# PCB.net
KiCad netlist of a schematic drawn in EAGLE
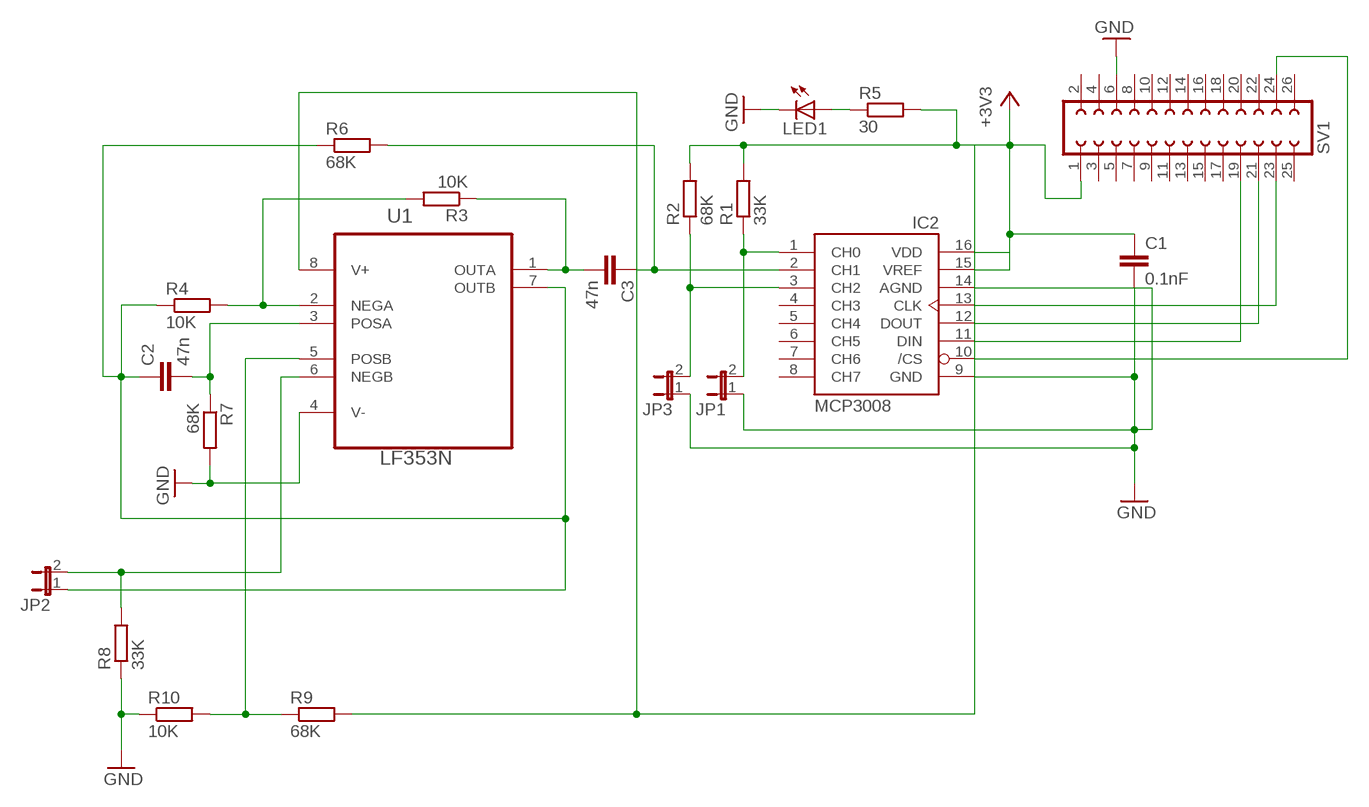
[diagram p0: schematic, sheet 1]

(export (version "E")
  (design (tool "Eeschema 10.0.6"))
  (components
    (comp (ref "C1")
      (value "0.1nF")
      (footprint "eagle-import:C050-035X075")
      (libsource (lib "eagle-import") (part "C-EU050-035X075"))
    )
    (comp (ref "C2")
      (value "47n")
      (footprint "eagle-import:C2.5-5")
      (libsource (lib "eagle-import") (part "C2.5/5"))
    )
    (comp (ref "C3")
      (value "47n")
      (footprint "eagle-import:C2.5-5")
      (libsource (lib "eagle-import") (part "C2.5/5"))
    )
    (comp (ref "IC2")
      (value "MCP3008")
      (footprint "eagle-import:DIL16")
      (libsource (lib "eagle-import") (part "MCP3008"))
    )
    (comp (ref "JP1")
      (value "JP1E")
      (footprint "eagle-import:JP1")
      (libsource (lib "eagle-import") (part "JP1E"))
    )
    (comp (ref "JP2")
      (value "JP1E")
      (footprint "eagle-import:JP1")
      (libsource (lib "eagle-import") (part "JP1E"))
    )
    (comp (ref "JP3")
      (value "JP1E")
      (footprint "eagle-import:JP1")
      (libsource (lib "eagle-import") (part "JP1E"))
    )
    (comp (ref "LED1")
      (value "LED5MM")
      (footprint "eagle-import:LED5MM")
      (libsource (lib "eagle-import") (part "LED5MM"))
    )
    (comp (ref "R1")
      (value "33K")
      (footprint "eagle-import:0207_10")
      (libsource (lib "eagle-import") (part "R-EU_0207/10"))
    )
    (comp (ref "R2")
      (value "68K")
      (footprint "eagle-import:0207_10")
      (libsource (lib "eagle-import") (part "R-EU_0207/10"))
    )
    (comp (ref "R3")
      (value "10K")
      (footprint "eagle-import:0207_10")
      (libsource (lib "eagle-import") (part "R-EU_0207/10"))
    )
    (comp (ref "R4")
      (value "10K")
      (footprint "eagle-import:0207_10")
      (libsource (lib "eagle-import") (part "R-EU_0207/10"))
    )
    (comp (ref "R5")
      (value "30")
      (footprint "eagle-import:0207_10")
      (libsource (lib "eagle-import") (part "R-EU_0207/10"))
    )
    (comp (ref "R6")
      (value "68K")
      (footprint "eagle-import:0207_10")
      (libsource (lib "eagle-import") (part "R-EU_0207/10"))
    )
    (comp (ref "R7")
      (value "68K")
      (footprint "eagle-import:0207_10")
      (libsource (lib "eagle-import") (part "R-EU_0207/10"))
    )
    (comp (ref "R8")
      (value "33K")
      (footprint "eagle-import:0207_10")
      (libsource (lib "eagle-import") (part "R-EU_0207/10"))
    )
    (comp (ref "R9")
      (value "68K")
      (footprint "eagle-import:0207_10")
      (libsource (lib "eagle-import") (part "R-EU_0207/10"))
    )
    (comp (ref "R10")
      (value "10K")
      (footprint "eagle-import:0207_10")
      (libsource (lib "eagle-import") (part "R-EU_0207/10"))
    )
    (comp (ref "SV1")
      (value "FE13-2")
      (footprint "eagle-import:FE13-2")
      (libsource (lib "eagle-import") (part "FE13-2"))
    )
    (comp (ref "U1")
      (value "LF353N")
      (footprint "eagle-import:DIP254P762X508-8")
      (fields (field (name "MF") "MCM Electronics"))
      (libsource (lib "eagle-import") (part "LF353N"))
    )
  )
  (nets
    (net (code "1") (name "+3V3") (class "Default")
      (node (ref "C1") (pin "1") (pinfunction "1_1") (pintype "passive"))
      (node (ref "IC2") (pin "15") (pinfunction "VREF_15") (pintype "input"))
      (node (ref "IC2") (pin "16") (pinfunction "VDD_16") (pintype "power_in"))
      (node (ref "R1") (pin "2") (pinfunction "2_2") (pintype "passive"))
      (node (ref "R2") (pin "2") (pinfunction "2_2") (pintype "passive"))
      (node (ref "R5") (pin "2") (pinfunction "2_2") (pintype "passive"))
      (node (ref "R9") (pin "2") (pinfunction "2_2") (pintype "passive"))
      (node (ref "SV1") (pin "1") (pinfunction "1_1") (pintype "passive"))
      (node (ref "U1") (pin "8") (pinfunction "V+_8") (pintype "power_in"))
    )
    (net (code "2") (name "GND") (class "Default")
      (node (ref "C1") (pin "2") (pinfunction "2_2") (pintype "passive"))
      (node (ref "IC2") (pin "14") (pinfunction "AGND_14") (pintype "power_in"))
      (node (ref "IC2") (pin "9") (pinfunction "GND_9") (pintype "power_in"))
      (node (ref "JP1") (pin "1") (pinfunction "1_1") (pintype "passive"))
      (node (ref "JP3") (pin "1") (pinfunction "1_1") (pintype "passive"))
      (node (ref "LED1") (pin "K") (pinfunction "C_K") (pintype "passive"))
      (node (ref "R10") (pin "1") (pinfunction "1_1") (pintype "passive"))
      (node (ref "R7") (pin "2") (pinfunction "2_2") (pintype "passive"))
      (node (ref "R8") (pin "1") (pinfunction "1_1") (pintype "passive"))
      (node (ref "SV1") (pin "6") (pinfunction "6_6") (pintype "passive"))
      (node (ref "U1") (pin "4") (pinfunction "V-_4") (pintype "power_in"))
    )
    (net (code "3") (name "Net-(IC2-CH0)") (class "Default")
      (node (ref "IC2") (pin "1") (pinfunction "CH0_1") (pintype "input"))
      (node (ref "JP1") (pin "2") (pinfunction "2_2") (pintype "passive"))
      (node (ref "R1") (pin "1") (pinfunction "1_1") (pintype "passive"))
    )
    (net (code "4") (name "Net-(IC2-CH1)") (class "Default")
      (node (ref "C3") (pin "1") (pinfunction "1_1") (pintype "passive"))
      (node (ref "IC2") (pin "2") (pinfunction "CH1_2") (pintype "input"))
      (node (ref "R6") (pin "2") (pinfunction "2_2") (pintype "passive"))
    )
    (net (code "5") (name "Net-(IC2-CH2)") (class "Default")
      (node (ref "IC2") (pin "3") (pinfunction "CH2_3") (pintype "input"))
      (node (ref "JP3") (pin "2") (pinfunction "2_2") (pintype "passive"))
      (node (ref "R2") (pin "1") (pinfunction "1_1") (pintype "passive"))
    )
    (net (code "6") (name "Net-(IC2-CLK)") (class "Default")
      (node (ref "IC2") (pin "13") (pinfunction "CLK_13") (pintype "input"))
      (node (ref "SV1") (pin "23") (pinfunction "23_23") (pintype "passive"))
    )
    (net (code "7") (name "Net-(IC2-DIN)") (class "Default")
      (node (ref "IC2") (pin "11") (pinfunction "DIN_11") (pintype "input"))
      (node (ref "SV1") (pin "19") (pinfunction "19_19") (pintype "passive"))
    )
    (net (code "8") (name "Net-(IC2-DOUT)") (class "Default")
      (node (ref "IC2") (pin "12") (pinfunction "DOUT_12") (pintype "output"))
      (node (ref "SV1") (pin "21") (pinfunction "21_21") (pintype "passive"))
    )
    (net (code "9") (name "Net-(IC2-{slash}CS)") (class "Default")
      (node (ref "IC2") (pin "10") (pinfunction "/CS_10") (pintype "input"))
      (node (ref "SV1") (pin "24") (pinfunction "24_24") (pintype "passive"))
    )
    (net (code "10") (name "Net-(LED1-PadA)") (class "Default")
      (node (ref "LED1") (pin "A") (pinfunction "A_A") (pintype "passive"))
      (node (ref "R5") (pin "1") (pinfunction "1_1") (pintype "passive"))
    )
    (net (code "11") (name "Net-(U1-NEGA)") (class "Default")
      (node (ref "R3") (pin "2") (pinfunction "2_2") (pintype "passive"))
      (node (ref "R4") (pin "2") (pinfunction "2_2") (pintype "passive"))
      (node (ref "U1") (pin "2") (pinfunction "NEGA_2") (pintype "input"))
    )
    (net (code "12") (name "Net-(U1-NEGB)") (class "Default")
      (node (ref "JP2") (pin "2") (pinfunction "2_2") (pintype "passive"))
      (node (ref "R8") (pin "2") (pinfunction "2_2") (pintype "passive"))
      (node (ref "U1") (pin "6") (pinfunction "NEGB_6") (pintype "input"))
    )
    (net (code "13") (name "Net-(U1-OUTA)") (class "Default")
      (node (ref "C3") (pin "2") (pinfunction "2_2") (pintype "passive"))
      (node (ref "R3") (pin "1") (pinfunction "1_1") (pintype "passive"))
      (node (ref "U1") (pin "1") (pinfunction "OUTA_1") (pintype "output"))
    )
    (net (code "14") (name "Net-(U1-OUTB)") (class "Default")
      (node (ref "C2") (pin "1") (pinfunction "1_1") (pintype "passive"))
      (node (ref "JP2") (pin "1") (pinfunction "1_1") (pintype "passive"))
      (node (ref "R4") (pin "1") (pinfunction "1_1") (pintype "passive"))
      (node (ref "R6") (pin "1") (pinfunction "1_1") (pintype "passive"))
      (node (ref "U1") (pin "7") (pinfunction "OUTB_7") (pintype "output"))
    )
    (net (code "15") (name "Net-(U1-POSA)") (class "Default")
      (node (ref "C2") (pin "2") (pinfunction "2_2") (pintype "passive"))
      (node (ref "R7") (pin "1") (pinfunction "1_1") (pintype "passive"))
      (node (ref "U1") (pin "3") (pinfunction "POSA_3") (pintype "input"))
    )
    (net (code "16") (name "Net-(U1-POSB)") (class "Default")
      (node (ref "R10") (pin "2") (pinfunction "2_2") (pintype "passive"))
      (node (ref "R9") (pin "1") (pinfunction "1_1") (pintype "passive"))
      (node (ref "U1") (pin "5") (pinfunction "POSB_5") (pintype "input"))
    )
    (net (code "17") (name "unconnected-(IC2-CH3-Pad4)") (class "Default")
      (node (ref "IC2") (pin "4") (pinfunction "CH3_4") (pintype "input"))
    )
    (net (code "18") (name "unconnected-(IC2-CH4-Pad5)") (class "Default")
      (node (ref "IC2") (pin "5") (pinfunction "CH4_5") (pintype "input"))
    )
    (net (code "19") (name "unconnected-(IC2-CH5-Pad6)") (class "Default")
      (node (ref "IC2") (pin "6") (pinfunction "CH5_6") (pintype "input"))
    )
    (net (code "20") (name "unconnected-(IC2-CH6-Pad7)") (class "Default")
      (node (ref "IC2") (pin "7") (pinfunction "CH6_7") (pintype "input"))
    )
    (net (code "21") (name "unconnected-(IC2-CH7-Pad8)") (class "Default")
      (node (ref "IC2") (pin "8") (pinfunction "CH7_8") (pintype "input"))
    )
    (net (code "22") (name "unconnected-(SV1-Pad2)") (class "Default")
      (node (ref "SV1") (pin "2") (pinfunction "2_2") (pintype "passive"))
    )
    (net (code "23") (name "unconnected-(SV1-Pad3)") (class "Default")
      (node (ref "SV1") (pin "3") (pinfunction "3_3") (pintype "passive"))
    )
    (net (code "24") (name "unconnected-(SV1-Pad4)") (class "Default")
      (node (ref "SV1") (pin "4") (pinfunction "4_4") (pintype "passive"))
    )
    (net (code "25") (name "unconnected-(SV1-Pad5)") (class "Default")
      (node (ref "SV1") (pin "5") (pinfunction "5_5") (pintype "passive"))
    )
    (net (code "26") (name "unconnected-(SV1-Pad7)") (class "Default")
      (node (ref "SV1") (pin "7") (pinfunction "7_7") (pintype "passive"))
    )
    (net (code "27") (name "unconnected-(SV1-Pad8)") (class "Default")
      (node (ref "SV1") (pin "8") (pinfunction "8_8") (pintype "passive"))
    )
    (net (code "28") (name "unconnected-(SV1-Pad9)") (class "Default")
      (node (ref "SV1") (pin "9") (pinfunction "9_9") (pintype "passive"))
    )
    (net (code "29") (name "unconnected-(SV1-Pad10)") (class "Default")
      (node (ref "SV1") (pin "10") (pinfunction "10_10") (pintype "passive"))
    )
    (net (code "30") (name "unconnected-(SV1-Pad11)") (class "Default")
      (node (ref "SV1") (pin "11") (pinfunction "11_11") (pintype "passive"))
    )
    (net (code "31") (name "unconnected-(SV1-Pad12)") (class "Default")
      (node (ref "SV1") (pin "12") (pinfunction "12_12") (pintype "passive"))
    )
    (net (code "32") (name "unconnected-(SV1-Pad13)") (class "Default")
      (node (ref "SV1") (pin "13") (pinfunction "13_13") (pintype "passive"))
    )
    (net (code "33") (name "unconnected-(SV1-Pad14)") (class "Default")
      (node (ref "SV1") (pin "14") (pinfunction "14_14") (pintype "passive"))
    )
    (net (code "34") (name "unconnected-(SV1-Pad15)") (class "Default")
      (node (ref "SV1") (pin "15") (pinfunction "15_15") (pintype "passive"))
    )
    (net (code "35") (name "unconnected-(SV1-Pad16)") (class "Default")
      (node (ref "SV1") (pin "16") (pinfunction "16_16") (pintype "passive"))
    )
    (net (code "36") (name "unconnected-(SV1-Pad17)") (class "Default")
      (node (ref "SV1") (pin "17") (pinfunction "17_17") (pintype "passive"))
    )
    (net (code "37") (name "unconnected-(SV1-Pad18)") (class "Default")
      (node (ref "SV1") (pin "18") (pinfunction "18_18") (pintype "passive"))
    )
    (net (code "38") (name "unconnected-(SV1-Pad20)") (class "Default")
      (node (ref "SV1") (pin "20") (pinfunction "20_20") (pintype "passive"))
    )
    (net (code "39") (name "unconnected-(SV1-Pad22)") (class "Default")
      (node (ref "SV1") (pin "22") (pinfunction "22_22") (pintype "passive"))
    )
    (net (code "40") (name "unconnected-(SV1-Pad25)") (class "Default")
      (node (ref "SV1") (pin "25") (pinfunction "25_25") (pintype "passive"))
    )
    (net (code "41") (name "unconnected-(SV1-Pad26)") (class "Default")
      (node (ref "SV1") (pin "26") (pinfunction "26_26") (pintype "passive"))
    )
  )
)
